# Numitron3.net
KiCad netlist of a schematic drawn in EAGLE
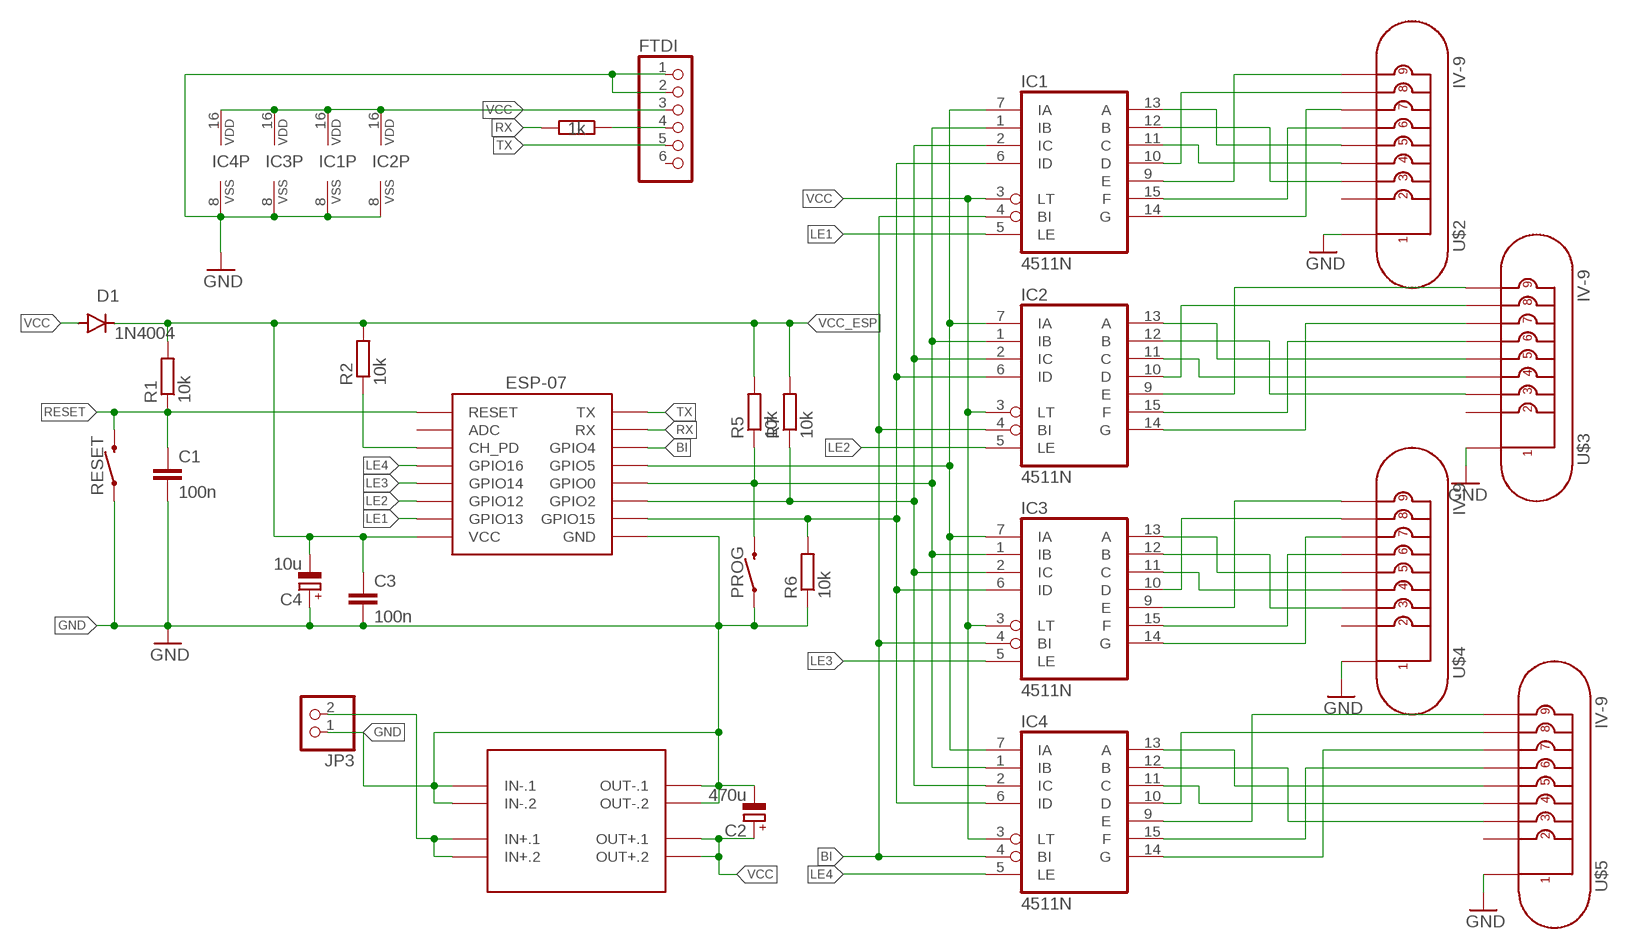
[diagram p0: schematic, sheet 1]

(export (version "E")
  (design (tool "Eeschema 10.0.6"))
  (components
    (comp (ref "C1")
      (value "100n")
      (footprint "eagle-import:C025-024X044")
      (libsource (lib "eagle-import") (part "C-EU025-024X044"))
    )
    (comp (ref "C2")
      (value "470u")
      (footprint "eagle-import:B45181B")
      (libsource (lib "eagle-import") (part "CPOL-EUB45181B"))
    )
    (comp (ref "C3")
      (value "100n")
      (footprint "eagle-import:C025-050X050")
      (libsource (lib "eagle-import") (part "C-EU025-050X050"))
    )
    (comp (ref "C4")
      (value "10u")
      (footprint "eagle-import:B45181A")
      (libsource (lib "eagle-import") (part "CPOL-EUB45181A"))
    )
    (comp (ref "D1")
      (value "1N4004")
      (footprint "eagle-import:DO41-10")
      (libsource (lib "eagle-import") (part "1N4004"))
    )
    (comp (ref "ESP-07")
      (value "ESP12SMD")
      (footprint "eagle-import:ESP12-SMD")
      (libsource (lib "eagle-import") (part "ESP12SMD"))
    )
    (comp (ref "FTDI")
      (value "PINHD-1X6")
      (footprint "eagle-import:1X06")
      (libsource (lib "eagle-import") (part "PINHD-1X6"))
    )
    (comp (ref "IC1")
      (value "4511N")
      (footprint "eagle-import:DIL16")
      (libsource (lib "eagle-import") (part "4511N"))
    )
    (comp (ref "IC2")
      (value "4511N")
      (footprint "eagle-import:DIL16")
      (libsource (lib "eagle-import") (part "4511N"))
    )
    (comp (ref "IC3")
      (value "4511N")
      (footprint "eagle-import:DIL16")
      (libsource (lib "eagle-import") (part "4511N"))
    )
    (comp (ref "IC4")
      (value "4511N")
      (footprint "eagle-import:DIL16")
      (libsource (lib "eagle-import") (part "4511N"))
    )
    (comp (ref "JP3")
      (value "PINHD-1X2")
      (footprint "eagle-import:1X02")
      (libsource (lib "eagle-import") (part "PINHD-1X2"))
    )
    (comp (ref "PROG")
      (value "MOMENTARY-SWITCH-SPST-PTH-6.0MM")
      (footprint "eagle-import:TACTILE_SWITCH_PTH_6.0MM")
      (libsource (lib "eagle-import") (part "MOMENTARY-SWITCH-SPST-PTH-6.0MM"))
    )
    (comp (ref "R1")
      (value "10k")
      (footprint "eagle-import:0204_7")
      (libsource (lib "eagle-import") (part "R-EU_0204/7"))
    )
    (comp (ref "R2")
      (value "10k")
      (footprint "eagle-import:0204_7")
      (libsource (lib "eagle-import") (part "R-EU_0204/7"))
    )
    (comp (ref "R4")
      (value "1k")
      (footprint "eagle-import:0204_7")
      (libsource (lib "eagle-import") (part "R-EU_0204/7"))
    )
    (comp (ref "R5")
      (value "10k")
      (footprint "eagle-import:0204_7")
      (libsource (lib "eagle-import") (part "R-EU_0204/7"))
    )
    (comp (ref "R6")
      (value "10k")
      (footprint "eagle-import:0204_7")
      (libsource (lib "eagle-import") (part "R-EU_0204/7"))
    )
    (comp (ref "R7")
      (value "10k")
      (footprint "eagle-import:0204_7")
      (libsource (lib "eagle-import") (part "R-EU_0204/7"))
    )
    (comp (ref "RESET")
      (value "MOMENTARY-SWITCH-SPST-PTH-6.0MM")
      (footprint "eagle-import:TACTILE_SWITCH_PTH_6.0MM")
      (libsource (lib "eagle-import") (part "MOMENTARY-SWITCH-SPST-PTH-6.0MM"))
    )
    (comp (ref "U$2")
      (value "IV-9")
      (footprint "eagle-import:IV-9")
      (libsource (lib "eagle-import") (part "IV-9"))
    )
    (comp (ref "U$3")
      (value "IV-9")
      (footprint "eagle-import:IV-9")
      (libsource (lib "eagle-import") (part "IV-9"))
    )
    (comp (ref "U$4")
      (value "IV-9")
      (footprint "eagle-import:IV-9")
      (libsource (lib "eagle-import") (part "IV-9"))
    )
    (comp (ref "U$5")
      (value "IV-9")
      (footprint "eagle-import:IV-9")
      (libsource (lib "eagle-import") (part "IV-9"))
    )
    (comp (ref "U$6")
      (value "DC-DC-STEP-DOWN-MP1584")
      (footprint "eagle-import:DC-DC-STEP-DOWN-MP1584")
      (libsource (lib "eagle-import") (part "DC-DC-STEP-DOWN-MP1584"))
    )
  )
  (nets
    (net (code "1") (name "BI") (class "Default")
      (node (ref "ESP-07") (pin "GPIO4") (pinfunction "GPIO4_GPIO4") (pintype "bidirectional"))
      (node (ref "IC1") (pin "4") (pinfunction "BI_4") (pintype "input"))
      (node (ref "IC2") (pin "4") (pinfunction "BI_4") (pintype "input"))
      (node (ref "IC3") (pin "4") (pinfunction "BI_4") (pintype "input"))
      (node (ref "IC4") (pin "4") (pinfunction "BI_4") (pintype "input"))
    )
    (net (code "2") (name "GND") (class "Default")
      (node (ref "C1") (pin "2") (pinfunction "2_2") (pintype "passive"))
      (node (ref "C2") (pin "-") (pinfunction "-_-") (pintype "passive"))
      (node (ref "C3") (pin "2") (pinfunction "2_2") (pintype "passive"))
      (node (ref "C4") (pin "+") (pinfunction "+_+") (pintype "passive"))
      (node (ref "ESP-07") (pin "GND") (pinfunction "GND_GND") (pintype "bidirectional"))
      (node (ref "FTDI") (pin "1") (pinfunction "1_1") (pintype "passive"))
      (node (ref "FTDI") (pin "2") (pinfunction "2_2") (pintype "passive"))
      (node (ref "IC1") (pin "8") (pinfunction "VSS_8") (pintype "power_in"))
      (node (ref "IC2") (pin "8") (pinfunction "VSS_8") (pintype "power_in"))
      (node (ref "IC3") (pin "8") (pinfunction "VSS_8") (pintype "power_in"))
      (node (ref "IC4") (pin "8") (pinfunction "VSS_8") (pintype "power_in"))
      (node (ref "JP3") (pin "1") (pinfunction "1_1") (pintype "passive"))
      (node (ref "PROG") (pin "1") (pinfunction "1_1") (pintype "passive"))
      (node (ref "R6") (pin "1") (pinfunction "1_1") (pintype "passive"))
      (node (ref "RESET") (pin "1") (pinfunction "1_1") (pintype "passive"))
      (node (ref "U$2") (pin "1") (pinfunction "1_1") (pintype "bidirectional"))
      (node (ref "U$3") (pin "1") (pinfunction "1_1") (pintype "bidirectional"))
      (node (ref "U$4") (pin "1") (pinfunction "1_1") (pintype "bidirectional"))
      (node (ref "U$5") (pin "1") (pinfunction "1_1") (pintype "bidirectional"))
      (node (ref "U$6") (pin "IN-.1") (pinfunction "IN-.1_IN-.1") (pintype "bidirectional"))
      (node (ref "U$6") (pin "IN-.2") (pinfunction "IN-.2_IN-.2") (pintype "bidirectional"))
      (node (ref "U$6") (pin "OUT-.1") (pinfunction "OUT-.1_OUT-.1") (pintype "bidirectional"))
      (node (ref "U$6") (pin "OUT-.2") (pinfunction "OUT-.2_OUT-.2") (pintype "bidirectional"))
    )
    (net (code "3") (name "LE1") (class "Default")
      (node (ref "ESP-07") (pin "GPIO13") (pinfunction "GPIO13_GPIO13") (pintype "bidirectional"))
      (node (ref "IC1") (pin "5") (pinfunction "LE_5") (pintype "input"))
    )
    (net (code "4") (name "LE2") (class "Default")
      (node (ref "ESP-07") (pin "GPIO12") (pinfunction "GPIO12_GPIO12") (pintype "bidirectional"))
      (node (ref "IC2") (pin "5") (pinfunction "LE_5") (pintype "input"))
    )
    (net (code "5") (name "LE3") (class "Default")
      (node (ref "ESP-07") (pin "GPIO14") (pinfunction "GPIO14_GPIO14") (pintype "bidirectional"))
      (node (ref "IC3") (pin "5") (pinfunction "LE_5") (pintype "input"))
    )
    (net (code "6") (name "LE4") (class "Default")
      (node (ref "ESP-07") (pin "GPIO16") (pinfunction "GPIO16_GPIO16") (pintype "bidirectional"))
      (node (ref "IC4") (pin "5") (pinfunction "LE_5") (pintype "input"))
    )
    (net (code "7") (name "Net-(ESP-07-PadCH_PD)") (class "Default")
      (node (ref "ESP-07") (pin "CH_PD") (pinfunction "CH_PD_CH_PD") (pintype "bidirectional"))
      (node (ref "R2") (pin "1") (pinfunction "1_1") (pintype "passive"))
    )
    (net (code "8") (name "Net-(FTDI-Pad4)") (class "Default")
      (node (ref "FTDI") (pin "4") (pinfunction "4_4") (pintype "passive"))
      (node (ref "R4") (pin "1") (pinfunction "1_1") (pintype "passive"))
    )
    (net (code "9") (name "Net-(IC1A-A)") (class "Default")
      (node (ref "IC1") (pin "13") (pinfunction "A_13") (pintype "output"))
      (node (ref "U$2") (pin "5") (pinfunction "5_5") (pintype "bidirectional"))
    )
    (net (code "10") (name "Net-(IC1A-B)") (class "Default")
      (node (ref "IC1") (pin "12") (pinfunction "B_12") (pintype "output"))
      (node (ref "U$2") (pin "3") (pinfunction "3_3") (pintype "bidirectional"))
    )
    (net (code "11") (name "Net-(IC1A-C)") (class "Default")
      (node (ref "IC1") (pin "11") (pinfunction "C_11") (pintype "output"))
      (node (ref "U$2") (pin "4") (pinfunction "4_4") (pintype "bidirectional"))
    )
    (net (code "12") (name "Net-(IC1A-D)") (class "Default")
      (node (ref "IC1") (pin "10") (pinfunction "D_10") (pintype "output"))
      (node (ref "U$2") (pin "8") (pinfunction "8_8") (pintype "bidirectional"))
    )
    (net (code "13") (name "Net-(IC1A-E)") (class "Default")
      (node (ref "IC1") (pin "9") (pinfunction "E_9") (pintype "output"))
      (node (ref "U$2") (pin "9") (pinfunction "9_9") (pintype "bidirectional"))
    )
    (net (code "14") (name "Net-(IC1A-F)") (class "Default")
      (node (ref "IC1") (pin "15") (pinfunction "F_15") (pintype "output"))
      (node (ref "U$2") (pin "6") (pinfunction "6_6") (pintype "bidirectional"))
    )
    (net (code "15") (name "Net-(IC1A-G)") (class "Default")
      (node (ref "IC1") (pin "14") (pinfunction "G_14") (pintype "output"))
      (node (ref "U$2") (pin "7") (pinfunction "7_7") (pintype "bidirectional"))
    )
    (net (code "16") (name "Net-(IC1A-IA)") (class "Default")
      (node (ref "ESP-07") (pin "GPIO5") (pinfunction "GPIO5_GPIO5") (pintype "bidirectional"))
      (node (ref "IC1") (pin "7") (pinfunction "IA_7") (pintype "input"))
      (node (ref "IC2") (pin "7") (pinfunction "IA_7") (pintype "input"))
      (node (ref "IC3") (pin "7") (pinfunction "IA_7") (pintype "input"))
      (node (ref "IC4") (pin "7") (pinfunction "IA_7") (pintype "input"))
    )
    (net (code "17") (name "Net-(IC1A-IB)") (class "Default")
      (node (ref "ESP-07") (pin "GPIO0") (pinfunction "GPIO0_GPIO0") (pintype "bidirectional"))
      (node (ref "IC1") (pin "1") (pinfunction "IB_1") (pintype "input"))
      (node (ref "IC2") (pin "1") (pinfunction "IB_1") (pintype "input"))
      (node (ref "IC3") (pin "1") (pinfunction "IB_1") (pintype "input"))
      (node (ref "IC4") (pin "1") (pinfunction "IB_1") (pintype "input"))
      (node (ref "PROG") (pin "3") (pinfunction "2_3") (pintype "passive"))
      (node (ref "R5") (pin "1") (pinfunction "1_1") (pintype "passive"))
    )
    (net (code "18") (name "Net-(IC1A-IC)") (class "Default")
      (node (ref "ESP-07") (pin "GPIO2") (pinfunction "GPIO2_GPIO2") (pintype "bidirectional"))
      (node (ref "IC1") (pin "2") (pinfunction "IC_2") (pintype "input"))
      (node (ref "IC2") (pin "2") (pinfunction "IC_2") (pintype "input"))
      (node (ref "IC3") (pin "2") (pinfunction "IC_2") (pintype "input"))
      (node (ref "IC4") (pin "2") (pinfunction "IC_2") (pintype "input"))
      (node (ref "R7") (pin "1") (pinfunction "1_1") (pintype "passive"))
    )
    (net (code "19") (name "Net-(IC1A-ID)") (class "Default")
      (node (ref "ESP-07") (pin "GPIO15") (pinfunction "GPIO15_GPIO15") (pintype "bidirectional"))
      (node (ref "IC1") (pin "6") (pinfunction "ID_6") (pintype "input"))
      (node (ref "IC2") (pin "6") (pinfunction "ID_6") (pintype "input"))
      (node (ref "IC3") (pin "6") (pinfunction "ID_6") (pintype "input"))
      (node (ref "IC4") (pin "6") (pinfunction "ID_6") (pintype "input"))
      (node (ref "R6") (pin "2") (pinfunction "2_2") (pintype "passive"))
    )
    (net (code "20") (name "Net-(IC2A-A)") (class "Default")
      (node (ref "IC2") (pin "13") (pinfunction "A_13") (pintype "output"))
      (node (ref "U$3") (pin "5") (pinfunction "5_5") (pintype "bidirectional"))
    )
    (net (code "21") (name "Net-(IC2A-B)") (class "Default")
      (node (ref "IC2") (pin "12") (pinfunction "B_12") (pintype "output"))
      (node (ref "U$3") (pin "3") (pinfunction "3_3") (pintype "bidirectional"))
    )
    (net (code "22") (name "Net-(IC2A-C)") (class "Default")
      (node (ref "IC2") (pin "11") (pinfunction "C_11") (pintype "output"))
      (node (ref "U$3") (pin "4") (pinfunction "4_4") (pintype "bidirectional"))
    )
    (net (code "23") (name "Net-(IC2A-D)") (class "Default")
      (node (ref "IC2") (pin "10") (pinfunction "D_10") (pintype "output"))
      (node (ref "U$3") (pin "8") (pinfunction "8_8") (pintype "bidirectional"))
    )
    (net (code "24") (name "Net-(IC2A-E)") (class "Default")
      (node (ref "IC2") (pin "9") (pinfunction "E_9") (pintype "output"))
      (node (ref "U$3") (pin "9") (pinfunction "9_9") (pintype "bidirectional"))
    )
    (net (code "25") (name "Net-(IC2A-F)") (class "Default")
      (node (ref "IC2") (pin "15") (pinfunction "F_15") (pintype "output"))
      (node (ref "U$3") (pin "6") (pinfunction "6_6") (pintype "bidirectional"))
    )
    (net (code "26") (name "Net-(IC2A-G)") (class "Default")
      (node (ref "IC2") (pin "14") (pinfunction "G_14") (pintype "output"))
      (node (ref "U$3") (pin "7") (pinfunction "7_7") (pintype "bidirectional"))
    )
    (net (code "27") (name "Net-(IC3A-A)") (class "Default")
      (node (ref "IC3") (pin "13") (pinfunction "A_13") (pintype "output"))
      (node (ref "U$4") (pin "5") (pinfunction "5_5") (pintype "bidirectional"))
    )
    (net (code "28") (name "Net-(IC3A-B)") (class "Default")
      (node (ref "IC3") (pin "12") (pinfunction "B_12") (pintype "output"))
      (node (ref "U$4") (pin "3") (pinfunction "3_3") (pintype "bidirectional"))
    )
    (net (code "29") (name "Net-(IC3A-C)") (class "Default")
      (node (ref "IC3") (pin "11") (pinfunction "C_11") (pintype "output"))
      (node (ref "U$4") (pin "4") (pinfunction "4_4") (pintype "bidirectional"))
    )
    (net (code "30") (name "Net-(IC3A-D)") (class "Default")
      (node (ref "IC3") (pin "10") (pinfunction "D_10") (pintype "output"))
      (node (ref "U$4") (pin "8") (pinfunction "8_8") (pintype "bidirectional"))
    )
    (net (code "31") (name "Net-(IC3A-E)") (class "Default")
      (node (ref "IC3") (pin "9") (pinfunction "E_9") (pintype "output"))
      (node (ref "U$4") (pin "9") (pinfunction "9_9") (pintype "bidirectional"))
    )
    (net (code "32") (name "Net-(IC3A-F)") (class "Default")
      (node (ref "IC3") (pin "15") (pinfunction "F_15") (pintype "output"))
      (node (ref "U$4") (pin "6") (pinfunction "6_6") (pintype "bidirectional"))
    )
    (net (code "33") (name "Net-(IC3A-G)") (class "Default")
      (node (ref "IC3") (pin "14") (pinfunction "G_14") (pintype "output"))
      (node (ref "U$4") (pin "7") (pinfunction "7_7") (pintype "bidirectional"))
    )
    (net (code "34") (name "Net-(IC4A-A)") (class "Default")
      (node (ref "IC4") (pin "13") (pinfunction "A_13") (pintype "output"))
      (node (ref "U$5") (pin "5") (pinfunction "5_5") (pintype "bidirectional"))
    )
    (net (code "35") (name "Net-(IC4A-B)") (class "Default")
      (node (ref "IC4") (pin "12") (pinfunction "B_12") (pintype "output"))
      (node (ref "U$5") (pin "3") (pinfunction "3_3") (pintype "bidirectional"))
    )
    (net (code "36") (name "Net-(IC4A-C)") (class "Default")
      (node (ref "IC4") (pin "11") (pinfunction "C_11") (pintype "output"))
      (node (ref "U$5") (pin "4") (pinfunction "4_4") (pintype "bidirectional"))
    )
    (net (code "37") (name "Net-(IC4A-D)") (class "Default")
      (node (ref "IC4") (pin "10") (pinfunction "D_10") (pintype "output"))
      (node (ref "U$5") (pin "8") (pinfunction "8_8") (pintype "bidirectional"))
    )
    (net (code "38") (name "Net-(IC4A-E)") (class "Default")
      (node (ref "IC4") (pin "9") (pinfunction "E_9") (pintype "output"))
      (node (ref "U$5") (pin "9") (pinfunction "9_9") (pintype "bidirectional"))
    )
    (net (code "39") (name "Net-(IC4A-F)") (class "Default")
      (node (ref "IC4") (pin "15") (pinfunction "F_15") (pintype "output"))
      (node (ref "U$5") (pin "6") (pinfunction "6_6") (pintype "bidirectional"))
    )
    (net (code "40") (name "Net-(IC4A-G)") (class "Default")
      (node (ref "IC4") (pin "14") (pinfunction "G_14") (pintype "output"))
      (node (ref "U$5") (pin "7") (pinfunction "7_7") (pintype "bidirectional"))
    )
    (net (code "41") (name "Net-(JP3-Pad2)") (class "Default")
      (node (ref "JP3") (pin "2") (pinfunction "2_2") (pintype "passive"))
      (node (ref "U$6") (pin "IN+.1") (pinfunction "IN+.1_IN+.1") (pintype "bidirectional"))
      (node (ref "U$6") (pin "IN+.2") (pinfunction "IN+.2_IN+.2") (pintype "bidirectional"))
    )
    (net (code "42") (name "RESET") (class "Default")
      (node (ref "C1") (pin "1") (pinfunction "1_1") (pintype "passive"))
      (node (ref "ESP-07") (pin "RESET") (pinfunction "RESET_RESET") (pintype "bidirectional"))
      (node (ref "R1") (pin "1") (pinfunction "1_1") (pintype "passive"))
      (node (ref "RESET") (pin "3") (pinfunction "2_3") (pintype "passive"))
    )
    (net (code "43") (name "RX") (class "Default")
      (node (ref "ESP-07") (pin "RXD0") (pinfunction "RX_RXD0") (pintype "bidirectional"))
      (node (ref "R4") (pin "2") (pinfunction "2_2") (pintype "passive"))
    )
    (net (code "44") (name "TX") (class "Default")
      (node (ref "ESP-07") (pin "TXD0") (pinfunction "TX_TXD0") (pintype "bidirectional"))
      (node (ref "FTDI") (pin "5") (pinfunction "5_5") (pintype "passive"))
    )
    (net (code "45") (name "VCC") (class "Default")
      (node (ref "C2") (pin "+") (pinfunction "+_+") (pintype "passive"))
      (node (ref "D1") (pin "A") (pinfunction "A_A") (pintype "passive"))
      (node (ref "FTDI") (pin "3") (pinfunction "3_3") (pintype "passive"))
      (node (ref "IC1") (pin "16") (pinfunction "VDD_16") (pintype "power_in"))
      (node (ref "IC1") (pin "3") (pinfunction "LT_3") (pintype "input"))
      (node (ref "IC2") (pin "16") (pinfunction "VDD_16") (pintype "power_in"))
      (node (ref "IC2") (pin "3") (pinfunction "LT_3") (pintype "input"))
      (node (ref "IC3") (pin "16") (pinfunction "VDD_16") (pintype "power_in"))
      (node (ref "IC3") (pin "3") (pinfunction "LT_3") (pintype "input"))
      (node (ref "IC4") (pin "16") (pinfunction "VDD_16") (pintype "power_in"))
      (node (ref "IC4") (pin "3") (pinfunction "LT_3") (pintype "input"))
      (node (ref "U$6") (pin "OUT+.1") (pinfunction "OUT+.1_OUT+.1") (pintype "bidirectional"))
      (node (ref "U$6") (pin "OUT+.2") (pinfunction "OUT+.2_OUT+.2") (pintype "bidirectional"))
    )
    (net (code "46") (name "VCC_ESP") (class "Default")
      (node (ref "C3") (pin "1") (pinfunction "1_1") (pintype "passive"))
      (node (ref "C4") (pin "-") (pinfunction "-_-") (pintype "passive"))
      (node (ref "D1") (pin "C") (pinfunction "C_C") (pintype "passive"))
      (node (ref "ESP-07") (pin "VCC") (pinfunction "VCC_VCC") (pintype "bidirectional"))
      (node (ref "R1") (pin "2") (pinfunction "2_2") (pintype "passive"))
      (node (ref "R2") (pin "2") (pinfunction "2_2") (pintype "passive"))
      (node (ref "R5") (pin "2") (pinfunction "2_2") (pintype "passive"))
      (node (ref "R7") (pin "2") (pinfunction "2_2") (pintype "passive"))
    )
    (net (code "47") (name "unconnected-(ESP-07-PadADC)") (class "Default")
      (node (ref "ESP-07") (pin "ADC") (pinfunction "ADC_ADC") (pintype "bidirectional"))
    )
    (net (code "48") (name "unconnected-(FTDI-Pad6)") (class "Default")
      (node (ref "FTDI") (pin "6") (pinfunction "6_6") (pintype "passive"))
    )
    (net (code "49") (name "unconnected-(U$2-Pad2)") (class "Default")
      (node (ref "U$2") (pin "2") (pinfunction "2_2") (pintype "bidirectional"))
    )
    (net (code "50") (name "unconnected-(U$3-Pad2)") (class "Default")
      (node (ref "U$3") (pin "2") (pinfunction "2_2") (pintype "bidirectional"))
    )
    (net (code "51") (name "unconnected-(U$4-Pad2)") (class "Default")
      (node (ref "U$4") (pin "2") (pinfunction "2_2") (pintype "bidirectional"))
    )
    (net (code "52") (name "unconnected-(U$5-Pad2)") (class "Default")
      (node (ref "U$5") (pin "2") (pinfunction "2_2") (pintype "bidirectional"))
    )
  )
)
